# 5v_led_charger.net
KiCad netlist of a schematic drawn in Altium Designer
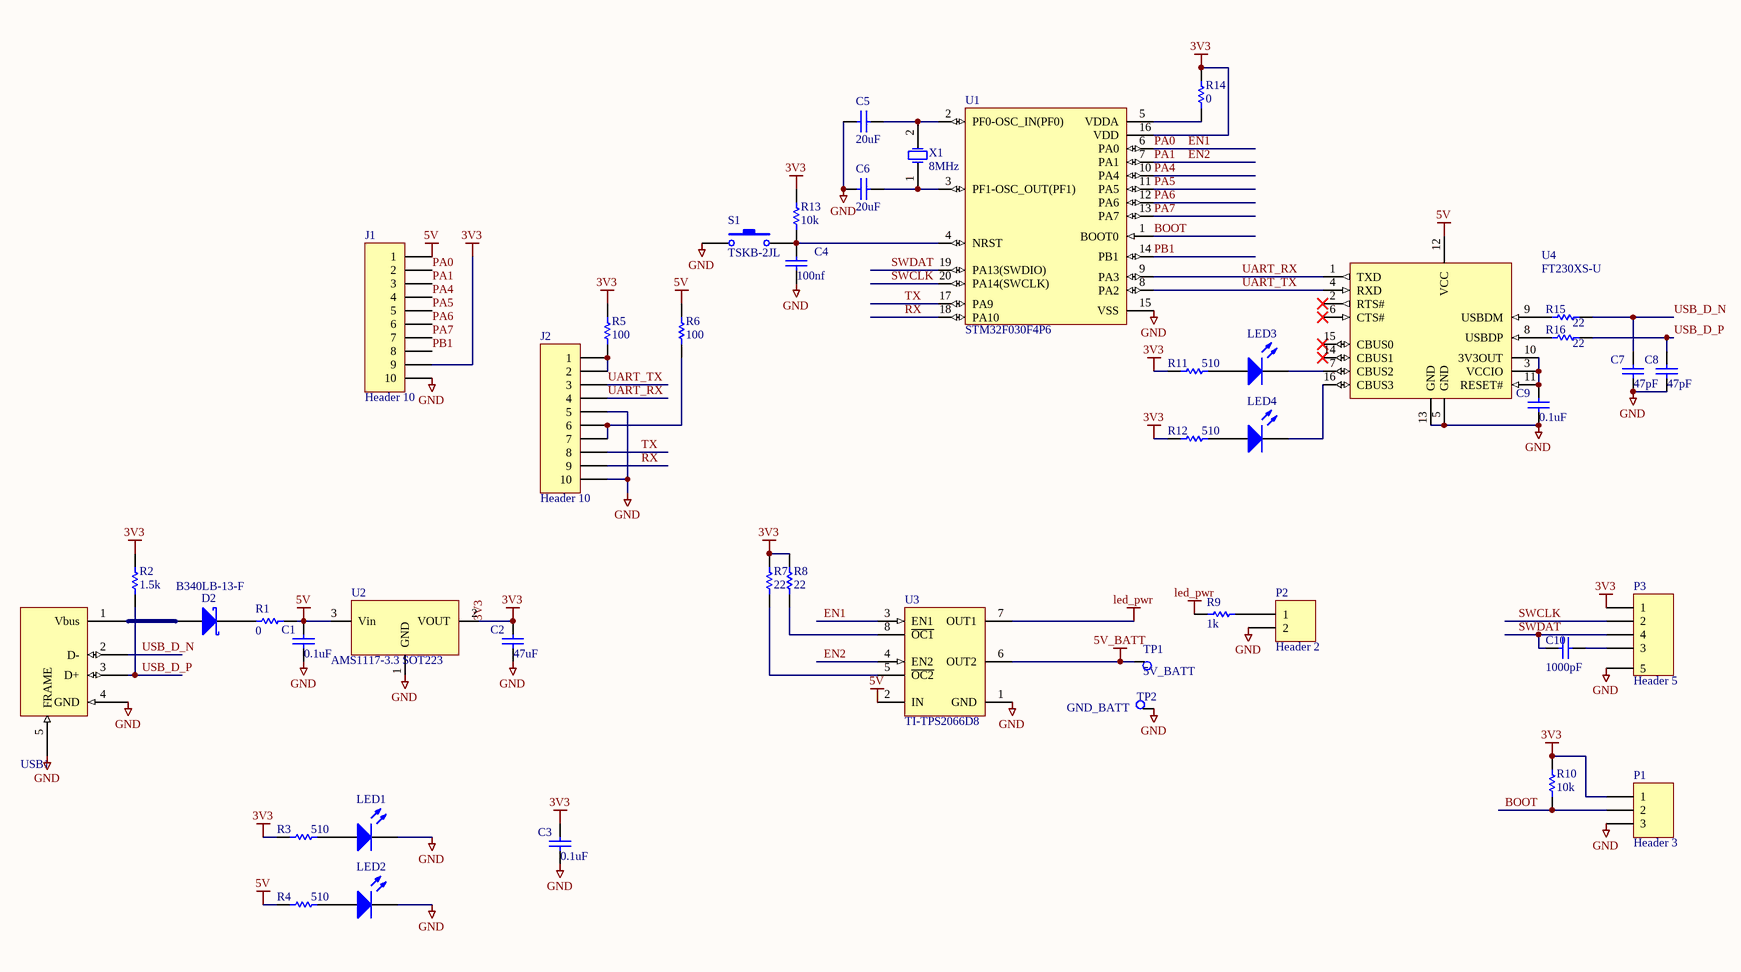
[diagram p0: 5v_led_charger.SchDoc]

(export (version "E")
  (design (tool "Eeschema 10.0.6"))
  (components
    (comp (ref "C1")
      (value "0.1uF")
      (footprint "1608[0603]")
      (description "Capacitor")
      (fields (field (name "PUBLISHER") "Altium Limited"))
      (libsource (lib "Miscellaneous Devices") (part "Cap"))
    )
    (comp (ref "C2")
      (value "47uF")
      (footprint "1608[0603]")
      (description "Capacitor")
      (fields (field (name "PUBLISHER") "Altium Limited"))
      (libsource (lib "Miscellaneous Devices") (part "Cap"))
    )
    (comp (ref "C3")
      (value "0.1uF")
      (footprint "1608[0603]")
      (description "Capacitor")
      (fields (field (name "PUBLISHER") "Altium Limited"))
      (libsource (lib "Miscellaneous Devices") (part "Cap"))
    )
    (comp (ref "C4")
      (value "100nf")
      (footprint "1608[0603]")
      (description "Capacitor")
      (fields (field (name "PUBLISHER") "Altium Limited"))
      (libsource (lib "Miscellaneous Devices") (part "Cap"))
    )
    (comp (ref "C5")
      (value "20uF")
      (footprint "1608[0603]")
      (description "Capacitor")
      (fields (field (name "PUBLISHER") "Altium Limited"))
      (libsource (lib "Miscellaneous Devices") (part "Cap"))
    )
    (comp (ref "C6")
      (value "20uF")
      (footprint "1608[0603]")
      (description "Capacitor")
      (fields (field (name "PUBLISHER") "Altium Limited"))
      (libsource (lib "Miscellaneous Devices") (part "Cap"))
    )
    (comp (ref "C7")
      (value "47pF")
      (footprint "1608[0603]")
      (description "Capacitor")
      (fields (field (name "PUBLISHER") "Altium Limited"))
      (libsource (lib "Miscellaneous Devices") (part "Cap"))
    )
    (comp (ref "C8")
      (value "47pF")
      (footprint "1608[0603]")
      (description "Capacitor")
      (fields (field (name "PUBLISHER") "Altium Limited"))
      (libsource (lib "Miscellaneous Devices") (part "Cap"))
    )
    (comp (ref "C9")
      (value "0.1uF")
      (footprint "1608[0603]")
      (description "Capacitor")
      (fields (field (name "PUBLISHER") "Altium Limited"))
      (libsource (lib "Miscellaneous Devices") (part "Cap"))
    )
    (comp (ref "C10")
      (value "1000pF")
      (footprint "1608[0603]")
      (description "Capacitor")
      (fields (field (name "PUBLISHER") "Altium Limited"))
      (libsource (lib "Miscellaneous Devices") (part "Cap"))
    )
    (comp (ref "D2")
      (value "B340LB-13-F")
      (footprint "DIOM4336X25N")
      (description "Schottky Diode")
      (fields (field (name "PUBLISHER") "Altium Limited"))
      (libsource (lib "Miscellaneous Devices") (part "D Schottky"))
    )
    (comp (ref "J1")
      (value "Header 10")
      (footprint "HDR1X10")
      (description "Header, 10-Pin")
      (fields (field (name "PUBLISHER") "Altium Limited"))
      (libsource (lib "JP_Integrated_lib") (part "Header 10"))
    )
    (comp (ref "J2")
      (value "Header 10")
      (footprint "HDR1X10")
      (description "Header, 10-Pin")
      (fields (field (name "PUBLISHER") "Altium Limited"))
      (libsource (lib "JP_Integrated_lib") (part "Header 10"))
    )
    (comp (ref "LED1")
      (value "LED2")
      (footprint "KING-0603LED_YELLOW_V")
      (description "Typical RED, GREEN, YELLOW, AMBER GaAs LED")
      (fields (field (name "PUBLISHER") "Altium Limited"))
      (libsource (lib "Miscellaneous Devices") (part "LED2"))
    )
    (comp (ref "LED2")
      (value "LED2")
      (footprint "KING-0603LED_GREEN_V")
      (description "Typical RED, GREEN, YELLOW, AMBER GaAs LED")
      (fields (field (name "PUBLISHER") "Altium Limited"))
      (libsource (lib "Miscellaneous Devices") (part "LED2"))
    )
    (comp (ref "LED3")
      (value "LED2")
      (footprint "KING-0603LED_GREEN_V")
      (description "Typical RED, GREEN, YELLOW, AMBER GaAs LED")
      (fields (field (name "PUBLISHER") "Altium Limited"))
      (libsource (lib "Miscellaneous Devices") (part "LED2"))
    )
    (comp (ref "LED4")
      (value "LED2")
      (footprint "KING-0603LED_ORANGE_V")
      (description "Typical RED, GREEN, YELLOW, AMBER GaAs LED")
      (fields (field (name "PUBLISHER") "Altium Limited"))
      (libsource (lib "Miscellaneous Devices") (part "LED2"))
    )
    (comp (ref "P1")
      (value "Header 3")
      (footprint "HDR1X3")
      (description "Header, 3-Pin")
      (fields (field (name "PUBLISHER") "Altium Limited"))
      (libsource (lib "JP_Integrated_lib") (part "Header 3"))
    )
    (comp (ref "P2")
      (value "Header 2")
      (footprint "HDR1X2")
      (description "Header, 2-Pin")
      (fields (field (name "PUBLISHER") "Altium Limited"))
      (libsource (lib "JP_Integrated_lib") (part "Header 2"))
    )
    (comp (ref "P3")
      (value "Header 5")
      (footprint "HDR1X5")
      (description "Header, 5-Pin")
      (fields (field (name "PUBLISHER") "Altium Limited"))
      (libsource (lib "JP_Integrated_lib") (part "Header 5"))
    )
    (comp (ref "R1")
      (value "0")
      (footprint "1608[0603]")
      (description "Resistor")
      (libsource (lib "Miscellaneous Devices") (part "Res1"))
    )
    (comp (ref "R2")
      (value "1.5k")
      (footprint "1608[0603]")
      (description "Resistor")
      (libsource (lib "Miscellaneous Devices") (part "Res1"))
    )
    (comp (ref "R3")
      (value "510")
      (footprint "1608[0603]")
      (description "Resistor")
      (libsource (lib "Miscellaneous Devices") (part "Res1"))
    )
    (comp (ref "R4")
      (value "510")
      (footprint "1608[0603]")
      (description "Resistor")
      (libsource (lib "Miscellaneous Devices") (part "Res1"))
    )
    (comp (ref "R5")
      (value "100")
      (footprint "1608[0603]")
      (description "Resistor")
      (libsource (lib "Miscellaneous Devices") (part "Res1"))
    )
    (comp (ref "R6")
      (value "100")
      (footprint "1608[0603]")
      (description "Resistor")
      (libsource (lib "Miscellaneous Devices") (part "Res1"))
    )
    (comp (ref "R7")
      (value "22")
      (footprint "1608[0603]")
      (description "Resistor")
      (libsource (lib "Miscellaneous Devices") (part "Res1"))
    )
    (comp (ref "R8")
      (value "22")
      (footprint "1608[0603]")
      (description "Resistor")
      (libsource (lib "Miscellaneous Devices") (part "Res1"))
    )
    (comp (ref "R9")
      (value "1k")
      (footprint "1608[0603]")
      (description "Resistor")
      (libsource (lib "Miscellaneous Devices") (part "Res1"))
    )
    (comp (ref "R10")
      (value "10k")
      (footprint "1608[0603]")
      (description "Resistor")
      (libsource (lib "Miscellaneous Devices") (part "Res1"))
    )
    (comp (ref "R11")
      (value "510")
      (footprint "1608[0603]")
      (description "Resistor")
      (libsource (lib "Miscellaneous Devices") (part "Res1"))
    )
    (comp (ref "R12")
      (value "510")
      (footprint "1608[0603]")
      (description "Resistor")
      (libsource (lib "Miscellaneous Devices") (part "Res1"))
    )
    (comp (ref "R13")
      (value "10k")
      (footprint "1608[0603]")
      (description "Resistor")
      (libsource (lib "Miscellaneous Devices") (part "Res1"))
    )
    (comp (ref "R14")
      (value "0")
      (footprint "1608[0603]")
      (description "Resistor")
      (libsource (lib "Miscellaneous Devices") (part "Res1"))
    )
    (comp (ref "R15")
      (value "22")
      (footprint "1608[0603]")
      (description "Resistor")
      (libsource (lib "Miscellaneous Devices") (part "Res1"))
    )
    (comp (ref "R16")
      (value "22")
      (footprint "1608[0603]")
      (description "Resistor")
      (libsource (lib "Miscellaneous Devices") (part "Res1"))
    )
    (comp (ref "S1")
      (value "TSKB-2JL")
      (footprint "TSKB-2JL")
      (description "Switch")
      (fields (field (name "PUBLISHER") "Altium Limited"))
      (libsource (lib "JP_Integrated_lib") (part "SW-PB"))
    )
    (comp (ref "TP1") (value "5V_BATT") (footprint "PAD1") (libsource (lib "ORIGINAL PARTS") (part "RAUND1")))
    (comp (ref "TP2")
      (value "GND_BATT")
      (footprint "PAD1")
      (libsource (lib "ORIGINAL PARTS") (part "RAUND1"))
    )
    (comp (ref "U1")
      (value "STM32F030F4P6")
      (footprint "STM-TSSOP20_L")
      (libsource (lib "Altium Content Vault") (part "CMP-0304-00039-2"))
    )
    (comp (ref "U2")
      (value "AMS1117-3.3 SOT223")
      (footprint "SOT223_L")
      (libsource (lib "JP_Integrated_lib") (part "AMS1117-3.3"))
    )
    (comp (ref "U3")
      (value "TI-TPS2066D8")
      (footprint "D8_L")
      (libsource (lib "altium-import") (part "root_0_SYM-0119-02368-1_"))
    )
    (comp (ref "U4")
      (value "FT230XS-U")
      (footprint "SSOP-16_L")
      (fields (field (name "MANUFACTURER") "FTDI"))
      (libsource (lib "Altium Content Vault") (part "CMP-0248-00025-2"))
    )
    (comp (ref "USB1")
      (value "USB002")
      (footprint "USB/SM0.8-6H5")
      (libsource (lib "ORIGINAL PARTS") (part "USB002"))
    )
    (comp (ref "X1")
      (value "8MHz")
      (footprint "ABRA-ABLS2-2_V")
      (fields (field (name "MANUFACTURER") "Abracon") (field (name "PARTNUMBER") "ABLS2-4.096MHZ-D4Y-T"))
      (libsource (lib "Altium Content Vault") (part "CMP-0277-00002-1"))
    )
  )
  (nets
    (net (code "1") (name "/BOOT") (class "Default")
      (node (ref "P1") (pin "2") (pinfunction "2_2") (pintype "passive"))
      (node (ref "R10") (pin "1") (pinfunction "1_1") (pintype "passive"))
      (node (ref "U1") (pin "1") (pinfunction "BOOT0_1") (pintype "input"))
    )
    (net (code "2") (name "/EN1") (class "Default")
      (node (ref "J1") (pin "2") (pinfunction "2_2") (pintype "passive"))
      (node (ref "U1") (pin "6") (pinfunction "PA0_6") (pintype "bidirectional"))
      (node (ref "U3") (pin "3") (pinfunction "EN1_3") (pintype "input"))
    )
    (net (code "3") (name "/EN2") (class "Default")
      (node (ref "J1") (pin "3") (pinfunction "3_3") (pintype "passive"))
      (node (ref "U1") (pin "7") (pinfunction "PA1_7") (pintype "bidirectional"))
      (node (ref "U3") (pin "4") (pinfunction "EN2_4") (pintype "input"))
    )
    (net (code "4") (name "/PA4") (class "Default")
      (node (ref "J1") (pin "4") (pinfunction "4_4") (pintype "passive"))
      (node (ref "U1") (pin "10") (pinfunction "PA4_10") (pintype "bidirectional"))
    )
    (net (code "5") (name "/PA5") (class "Default")
      (node (ref "J1") (pin "5") (pinfunction "5_5") (pintype "passive"))
      (node (ref "U1") (pin "11") (pinfunction "PA5_11") (pintype "bidirectional"))
    )
    (net (code "6") (name "/PA6") (class "Default")
      (node (ref "J1") (pin "6") (pinfunction "6_6") (pintype "passive"))
      (node (ref "U1") (pin "12") (pinfunction "PA6_12") (pintype "bidirectional"))
    )
    (net (code "7") (name "/PA7") (class "Default")
      (node (ref "J1") (pin "7") (pinfunction "7_7") (pintype "passive"))
      (node (ref "U1") (pin "13") (pinfunction "PA7_13") (pintype "bidirectional"))
    )
    (net (code "8") (name "/PB1") (class "Default")
      (node (ref "J1") (pin "8") (pinfunction "8_8") (pintype "passive"))
      (node (ref "U1") (pin "14") (pinfunction "PB1_14") (pintype "bidirectional"))
    )
    (net (code "9") (name "/RX") (class "Default")
      (node (ref "J2") (pin "9") (pinfunction "9_9") (pintype "passive"))
      (node (ref "U1") (pin "18") (pinfunction "PA10_18") (pintype "bidirectional"))
    )
    (net (code "10") (name "/SWCLK") (class "Default")
      (node (ref "P3") (pin "2") (pinfunction "2_2") (pintype "passive"))
      (node (ref "U1") (pin "20") (pinfunction "PA14(SWCLK)_20") (pintype "bidirectional"))
    )
    (net (code "11") (name "/SWDAT") (class "Default")
      (node (ref "C10") (pin "1") (pinfunction "1_1") (pintype "passive"))
      (node (ref "P3") (pin "4") (pinfunction "4_4") (pintype "passive"))
      (node (ref "U1") (pin "19") (pinfunction "PA13(SWDIO)_19") (pintype "bidirectional"))
    )
    (net (code "12") (name "/TX") (class "Default")
      (node (ref "J2") (pin "8") (pinfunction "8_8") (pintype "passive"))
      (node (ref "U1") (pin "17") (pinfunction "PA9_17") (pintype "bidirectional"))
    )
    (net (code "13") (name "/UART_RX") (class "Default")
      (node (ref "J2") (pin "4") (pinfunction "4_4") (pintype "passive"))
      (node (ref "U1") (pin "9") (pinfunction "PA3_9") (pintype "bidirectional"))
      (node (ref "U4") (pin "1") (pinfunction "TXD_1") (pintype "output"))
    )
    (net (code "14") (name "/UART_TX") (class "Default")
      (node (ref "J2") (pin "3") (pinfunction "3_3") (pintype "passive"))
      (node (ref "U1") (pin "8") (pinfunction "PA2_8") (pintype "bidirectional"))
      (node (ref "U4") (pin "4") (pinfunction "RXD_4") (pintype "input"))
    )
    (net (code "15") (name "/USB_D_N") (class "Default")
      (node (ref "C7") (pin "2") (pinfunction "2_2") (pintype "passive"))
      (node (ref "R15") (pin "1") (pinfunction "1_1") (pintype "passive"))
      (node (ref "USB1") (pin "2") (pinfunction "D-_2") (pintype "bidirectional"))
    )
    (net (code "16") (name "/USB_D_P") (class "Default")
      (node (ref "C8") (pin "2") (pinfunction "2_2") (pintype "passive"))
      (node (ref "R16") (pin "1") (pinfunction "1_1") (pintype "passive"))
      (node (ref "R2") (pin "2") (pinfunction "2_2") (pintype "passive"))
      (node (ref "USB1") (pin "3") (pinfunction "D+_3") (pintype "bidirectional"))
    )
    (net (code "17") (name "3V3") (class "Default")
      (node (ref "C2") (pin "2") (pinfunction "2_2") (pintype "passive"))
      (node (ref "C3") (pin "2") (pinfunction "2_2") (pintype "passive"))
      (node (ref "J1") (pin "9") (pinfunction "9_9") (pintype "passive"))
      (node (ref "P1") (pin "1") (pinfunction "1_1") (pintype "passive"))
      (node (ref "P3") (pin "1") (pinfunction "1_1") (pintype "passive"))
      (node (ref "R10") (pin "2") (pinfunction "2_2") (pintype "passive"))
      (node (ref "R11") (pin "2") (pinfunction "2_2") (pintype "passive"))
      (node (ref "R12") (pin "2") (pinfunction "2_2") (pintype "passive"))
      (node (ref "R13") (pin "1") (pinfunction "1_1") (pintype "passive"))
      (node (ref "R14") (pin "1") (pinfunction "1_1") (pintype "passive"))
      (node (ref "R2") (pin "1") (pinfunction "1_1") (pintype "passive"))
      (node (ref "R3") (pin "2") (pinfunction "2_2") (pintype "passive"))
      (node (ref "R5") (pin "1") (pinfunction "1_1") (pintype "passive"))
      (node (ref "R7") (pin "1") (pinfunction "1_1") (pintype "passive"))
      (node (ref "R8") (pin "1") (pinfunction "1_1") (pintype "passive"))
      (node (ref "U1") (pin "16") (pinfunction "VDD_16") (pintype "power_in"))
      (node (ref "U2") (pin "2") (pinfunction "VOUT_2") (pintype "power_in"))
    )
    (net (code "18") (name "5V") (class "Default")
      (node (ref "C1") (pin "2") (pinfunction "2_2") (pintype "passive"))
      (node (ref "J1") (pin "1") (pinfunction "1_1") (pintype "passive"))
      (node (ref "R1") (pin "1") (pinfunction "1_1") (pintype "passive"))
      (node (ref "R4") (pin "2") (pinfunction "2_2") (pintype "passive"))
      (node (ref "R6") (pin "1") (pinfunction "1_1") (pintype "passive"))
      (node (ref "U2") (pin "3") (pinfunction "Vin_3") (pintype "power_in"))
      (node (ref "U3") (pin "2") (pinfunction "IN_2") (pintype "power_in"))
      (node (ref "U4") (pin "12") (pinfunction "VCC_12") (pintype "power_in"))
    )
    (net (code "19") (name "5V_BATT") (class "Default")
      (node (ref "TP1") (pin "1") (pinfunction "1_1") (pintype "passive"))
      (node (ref "U3") (pin "6") (pinfunction "OUT2_6") (pintype "power_in"))
    )
    (net (code "20") (name "GND") (class "Default")
      (node (ref "C1") (pin "1") (pinfunction "1_1") (pintype "passive"))
      (node (ref "C2") (pin "1") (pinfunction "1_1") (pintype "passive"))
      (node (ref "C3") (pin "1") (pinfunction "1_1") (pintype "passive"))
      (node (ref "C4") (pin "1") (pinfunction "1_1") (pintype "passive"))
      (node (ref "C5") (pin "2") (pinfunction "2_2") (pintype "passive"))
      (node (ref "C6") (pin "2") (pinfunction "2_2") (pintype "passive"))
      (node (ref "C7") (pin "1") (pinfunction "1_1") (pintype "passive"))
      (node (ref "C8") (pin "1") (pinfunction "1_1") (pintype "passive"))
      (node (ref "C9") (pin "1") (pinfunction "1_1") (pintype "passive"))
      (node (ref "J1") (pin "10") (pinfunction "10_10") (pintype "passive"))
      (node (ref "J2") (pin "10") (pinfunction "10_10") (pintype "passive"))
      (node (ref "J2") (pin "5") (pinfunction "5_5") (pintype "passive"))
      (node (ref "LED1") (pin "2") (pinfunction "K_2") (pintype "passive"))
      (node (ref "LED2") (pin "2") (pinfunction "K_2") (pintype "passive"))
      (node (ref "P1") (pin "3") (pinfunction "3_3") (pintype "passive"))
      (node (ref "P2") (pin "2") (pinfunction "2_2") (pintype "passive"))
      (node (ref "P3") (pin "5") (pinfunction "5_5") (pintype "passive"))
      (node (ref "S1") (pin "1") (pinfunction "1_1") (pintype "passive"))
      (node (ref "TP2") (pin "1") (pinfunction "1_1") (pintype "passive"))
      (node (ref "U1") (pin "15") (pinfunction "VSS_15") (pintype "power_in"))
      (node (ref "U2") (pin "1") (pinfunction "GND_1") (pintype "passive"))
      (node (ref "U3") (pin "1") (pinfunction "GND_1") (pintype "power_in"))
      (node (ref "U4") (pin "13") (pinfunction "GND_13") (pintype "power_in"))
      (node (ref "U4") (pin "5") (pinfunction "GND_5") (pintype "power_in"))
      (node (ref "USB1") (pin "4") (pinfunction "GND_4") (pintype "input"))
      (node (ref "USB1") (pin "5") (pinfunction "FRAME_5") (pintype "input"))
    )
    (net (code "21") (name "Net-(C10-Pad2)") (class "Default")
      (node (ref "C10") (pin "2") (pinfunction "2_2") (pintype "passive"))
      (node (ref "P3") (pin "3") (pinfunction "3_3") (pintype "passive"))
    )
    (net (code "22") (name "Net-(D2-A)") (class "Default")
      (node (ref "D2") (pin "1") (pinfunction "A_1") (pintype "passive"))
      (node (ref "USB1") (pin "1") (pinfunction "Vbus_1") (pintype "power_in"))
    )
    (net (code "23") (name "Net-(D2-K)") (class "Default")
      (node (ref "D2") (pin "2") (pinfunction "K_2") (pintype "passive"))
      (node (ref "R1") (pin "2") (pinfunction "2_2") (pintype "passive"))
    )
    (net (code "24") (name "Net-(J2-Pad1)") (class "Default")
      (node (ref "J2") (pin "1") (pinfunction "1_1") (pintype "passive"))
      (node (ref "J2") (pin "2") (pinfunction "2_2") (pintype "passive"))
      (node (ref "R5") (pin "2") (pinfunction "2_2") (pintype "passive"))
    )
    (net (code "25") (name "Net-(J2-Pad6)") (class "Default")
      (node (ref "J2") (pin "6") (pinfunction "6_6") (pintype "passive"))
      (node (ref "J2") (pin "7") (pinfunction "7_7") (pintype "passive"))
      (node (ref "R6") (pin "2") (pinfunction "2_2") (pintype "passive"))
    )
    (net (code "26") (name "Net-(LED1-A)") (class "Default")
      (node (ref "LED1") (pin "1") (pinfunction "A_1") (pintype "passive"))
      (node (ref "R3") (pin "1") (pinfunction "1_1") (pintype "passive"))
    )
    (net (code "27") (name "Net-(LED2-A)") (class "Default")
      (node (ref "LED2") (pin "1") (pinfunction "A_1") (pintype "passive"))
      (node (ref "R4") (pin "1") (pinfunction "1_1") (pintype "passive"))
    )
    (net (code "28") (name "Net-(LED3-A)") (class "Default")
      (node (ref "LED3") (pin "1") (pinfunction "A_1") (pintype "passive"))
      (node (ref "R11") (pin "1") (pinfunction "1_1") (pintype "passive"))
    )
    (net (code "29") (name "Net-(LED3-K)") (class "Default")
      (node (ref "LED3") (pin "2") (pinfunction "K_2") (pintype "passive"))
      (node (ref "U4") (pin "7") (pinfunction "CBUS2_7") (pintype "bidirectional"))
    )
    (net (code "30") (name "Net-(LED4-A)") (class "Default")
      (node (ref "LED4") (pin "1") (pinfunction "A_1") (pintype "passive"))
      (node (ref "R12") (pin "1") (pinfunction "1_1") (pintype "passive"))
    )
    (net (code "31") (name "Net-(LED4-K)") (class "Default")
      (node (ref "LED4") (pin "2") (pinfunction "K_2") (pintype "passive"))
      (node (ref "U4") (pin "16") (pinfunction "CBUS3_16") (pintype "bidirectional"))
    )
    (net (code "32") (name "Net-(P2-Pad1)") (class "Default")
      (node (ref "P2") (pin "1") (pinfunction "1_1") (pintype "passive"))
      (node (ref "R9") (pin "2") (pinfunction "2_2") (pintype "passive"))
    )
    (net (code "33") (name "Net-(U1-NRST)") (class "Default")
      (node (ref "C4") (pin "2") (pinfunction "2_2") (pintype "passive"))
      (node (ref "R13") (pin "2") (pinfunction "2_2") (pintype "passive"))
      (node (ref "S1") (pin "2") (pinfunction "2_2") (pintype "passive"))
      (node (ref "U1") (pin "4") (pinfunction "NRST_4") (pintype "bidirectional"))
    )
    (net (code "34") (name "Net-(U1-PF0-OSC_IN(PF0))") (class "Default")
      (node (ref "C5") (pin "1") (pinfunction "1_1") (pintype "passive"))
      (node (ref "U1") (pin "2") (pinfunction "PF0-OSC_IN(PF0)_2") (pintype "bidirectional"))
      (node (ref "X1") (pin "2") (pinfunction "X2_2") (pintype "passive"))
    )
    (net (code "35") (name "Net-(U1-PF1-OSC_OUT(PF1))") (class "Default")
      (node (ref "C6") (pin "1") (pinfunction "1_1") (pintype "passive"))
      (node (ref "U1") (pin "3") (pinfunction "PF1-OSC_OUT(PF1)_3") (pintype "bidirectional"))
      (node (ref "X1") (pin "1") (pinfunction "X1_1") (pintype "passive"))
    )
    (net (code "36") (name "Net-(U1-VDDA)") (class "Default")
      (node (ref "R14") (pin "2") (pinfunction "2_2") (pintype "passive"))
      (node (ref "U1") (pin "5") (pinfunction "VDDA_5") (pintype "power_in"))
    )
    (net (code "37") (name "Net-(U3-~{OC1})") (class "Default")
      (node (ref "R8") (pin "2") (pinfunction "2_2") (pintype "passive"))
      (node (ref "U3") (pin "8") (pinfunction "~{OC1}_8") (pintype "open_collector"))
    )
    (net (code "38") (name "Net-(U3-~{OC2})") (class "Default")
      (node (ref "R7") (pin "2") (pinfunction "2_2") (pintype "passive"))
      (node (ref "U3") (pin "5") (pinfunction "~{OC2}_5") (pintype "open_collector"))
    )
    (net (code "39") (name "Net-(U4-3V3OUT)") (class "Default")
      (node (ref "C9") (pin "2") (pinfunction "2_2") (pintype "passive"))
      (node (ref "U4") (pin "10") (pinfunction "3V3OUT_10") (pintype "power_in"))
      (node (ref "U4") (pin "11") (pinfunction "RESET#_11") (pintype "input"))
      (node (ref "U4") (pin "3") (pinfunction "VCCIO_3") (pintype "power_in"))
    )
    (net (code "40") (name "Net-(U4-USBDM)") (class "Default")
      (node (ref "R15") (pin "2") (pinfunction "2_2") (pintype "passive"))
      (node (ref "U4") (pin "9") (pinfunction "USBDM_9") (pintype "input"))
    )
    (net (code "41") (name "Net-(U4-USBDP)") (class "Default")
      (node (ref "R16") (pin "2") (pinfunction "2_2") (pintype "passive"))
      (node (ref "U4") (pin "8") (pinfunction "USBDP_8") (pintype "input"))
    )
    (net (code "42") (name "led_pwr") (class "Default")
      (node (ref "R9") (pin "1") (pinfunction "1_1") (pintype "passive"))
      (node (ref "U3") (pin "7") (pinfunction "OUT1_7") (pintype "power_in"))
    )
    (net (code "43") (name "unconnected-(U4-CBUS0-Pad15)") (class "Default")
      (node (ref "U4") (pin "15") (pinfunction "CBUS0_15") (pintype "bidirectional+no_connect"))
    )
    (net (code "44") (name "unconnected-(U4-CBUS1-Pad14)") (class "Default")
      (node (ref "U4") (pin "14") (pinfunction "CBUS1_14") (pintype "bidirectional+no_connect"))
    )
    (net (code "45") (name "unconnected-(U4-CTS#-Pad6)") (class "Default")
      (node (ref "U4") (pin "6") (pinfunction "CTS#_6") (pintype "input+no_connect"))
    )
    (net (code "46") (name "unconnected-(U4-RTS#-Pad2)") (class "Default")
      (node (ref "U4") (pin "2") (pinfunction "RTS#_2") (pintype "output+no_connect"))
    )
  )
)
